# TSAL_Proto18_rev3_1.net
KiCad netlist of a schematic drawn in EAGLE
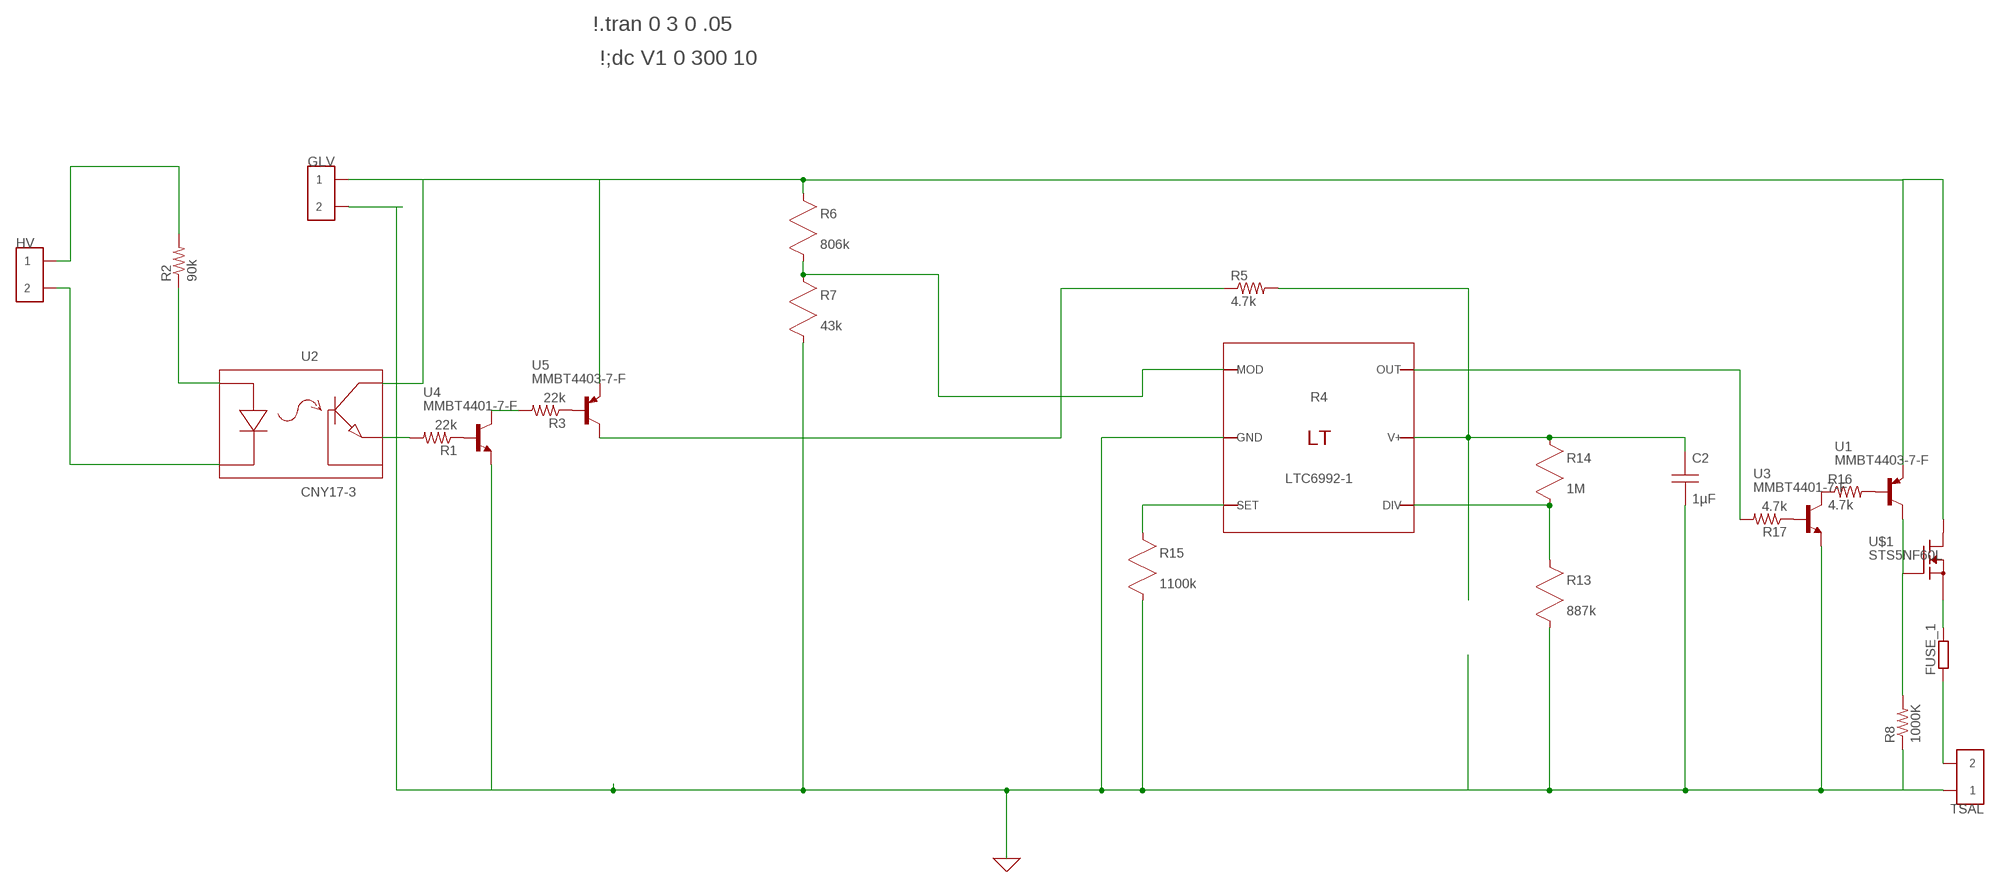
[diagram p0: schematic, sheet 1]

(export (version "E")
  (design (tool "Eeschema 10.0.6"))
  (components
    (comp (ref "C2")
      (value "1µF")
      (footprint "eagle-import:C0805")
      (libsource (lib "eagle-import") (part "CAP"))
    )
    (comp (ref "FUSE_1")
      (value "R-EU_R0402")
      (footprint "eagle-import:R0402")
      (libsource (lib "eagle-import") (part "R-EU_R0402"))
    )
    (comp (ref "GLV")
      (value "CONN_2")
      (footprint "eagle-import:CONNECTOR_2")
      (libsource (lib "eagle-import") (part "CONN_2"))
    )
    (comp (ref "HV")
      (value "CONN_2")
      (footprint "eagle-import:CONNECTOR_2")
      (libsource (lib "eagle-import") (part "CONN_2"))
    )
    (comp (ref "R1")
      (value "22k")
      (footprint "eagle-import:R0402")
      (libsource (lib "eagle-import") (part "R-US_R0402"))
    )
    (comp (ref "R2")
      (value "90k")
      (footprint "eagle-import:P0817_22")
      (libsource (lib "eagle-import") (part "R-US_0817/22"))
    )
    (comp (ref "R3")
      (value "22k")
      (footprint "eagle-import:R0402")
      (libsource (lib "eagle-import") (part "R-US_R0402"))
    )
    (comp (ref "R4")
      (value "LTC6992-1")
      (footprint "eagle-import:LTC6992-1")
      (libsource (lib "eagle-import") (part "LTC6992-1"))
    )
    (comp (ref "R5")
      (value "4.7k")
      (footprint "eagle-import:0805")
      (libsource (lib "eagle-import") (part "RESISTOR0805-RES"))
    )
    (comp (ref "R6")
      (value "806k")
      (footprint "eagle-import:R0805")
      (libsource (lib "eagle-import") (part "RES"))
    )
    (comp (ref "R7")
      (value "43k")
      (footprint "eagle-import:R0805")
      (libsource (lib "eagle-import") (part "RES"))
    )
    (comp (ref "R8")
      (value "1000K")
      (footprint "eagle-import:0805")
      (libsource (lib "eagle-import") (part "RESISTOR0805-RES"))
    )
    (comp (ref "R13")
      (value "887k")
      (footprint "eagle-import:R0805")
      (libsource (lib "eagle-import") (part "RES"))
    )
    (comp (ref "R14")
      (value "1M")
      (footprint "eagle-import:R0805")
      (libsource (lib "eagle-import") (part "RES"))
    )
    (comp (ref "R15")
      (value "1100k")
      (footprint "eagle-import:R0805")
      (libsource (lib "eagle-import") (part "RES"))
    )
    (comp (ref "R16")
      (value "4.7k")
      (footprint "eagle-import:R0402")
      (libsource (lib "eagle-import") (part "R-US_R0402"))
    )
    (comp (ref "R17")
      (value "4.7k")
      (footprint "eagle-import:R0402")
      (libsource (lib "eagle-import") (part "R-US_R0402"))
    )
    (comp (ref "TSAL")
      (value "CONN_2")
      (footprint "eagle-import:CONNECTOR_2")
      (libsource (lib "eagle-import") (part "CONN_2"))
    )
    (comp (ref "U$1")
      (value "STS5NF60L")
      (footprint "eagle-import:SO08")
      (libsource (lib "eagle-import") (part "STS5NF60L"))
    )
    (comp (ref "U1")
      (value "MMBT4403-7-F")
      (footprint "eagle-import:SOT-23-3")
      (libsource (lib "eagle-import") (part "MMBT4403-7-F"))
    )
    (comp (ref "U2")
      (value "CNY17-3")
      (footprint "eagle-import:CNY17-3")
      (libsource (lib "eagle-import") (part "CNY17-3"))
    )
    (comp (ref "U3")
      (value "MMBT4401-7-F")
      (footprint "eagle-import:SOT-23-3")
      (libsource (lib "eagle-import") (part "MMBT4401-7-F"))
    )
    (comp (ref "U4")
      (value "MMBT4401-7-F")
      (footprint "eagle-import:SOT-23-3")
      (libsource (lib "eagle-import") (part "MMBT4401-7-F"))
    )
    (comp (ref "U5")
      (value "MMBT4403-7-F")
      (footprint "eagle-import:SOT-23-3")
      (libsource (lib "eagle-import") (part "MMBT4403-7-F"))
    )
  )
  (nets
    (net (code "1") (name "0") (class "Default")
      (node (ref "C2") (pin "2") (pinfunction "B_2") (pintype "passive"))
      (node (ref "GLV") (pin "3") (pinfunction "2_3") (pintype "bidirectional"))
      (node (ref "GLV") (pin "4") (pinfunction "2_4") (pintype "bidirectional"))
      (node (ref "R13") (pin "2") (pinfunction "B_2") (pintype "passive"))
      (node (ref "R15") (pin "2") (pinfunction "B_2") (pintype "passive"))
      (node (ref "R4") (pin "P$2") (pinfunction "GND_P$2") (pintype "passive"))
      (node (ref "R7") (pin "2") (pinfunction "B_2") (pintype "passive"))
      (node (ref "R8") (pin "1") (pinfunction "1_1") (pintype "passive"))
      (node (ref "TSAL") (pin "1") (pinfunction "1_1") (pintype "bidirectional"))
      (node (ref "TSAL") (pin "2") (pinfunction "1_2") (pintype "bidirectional"))
      (node (ref "U3") (pin "P$3") (pinfunction "E_P$3") (pintype "passive"))
      (node (ref "U4") (pin "P$3") (pinfunction "E_P$3") (pintype "passive"))
    )
    (net (code "2") (name "Net-(C2-A)") (class "Default")
      (node (ref "C2") (pin "1") (pinfunction "A_1") (pintype "passive"))
      (node (ref "R14") (pin "1") (pinfunction "A_1") (pintype "passive"))
      (node (ref "R4") (pin "P$5") (pinfunction "V+_P$5") (pintype "passive"))
      (node (ref "R5") (pin "2") (pinfunction "2_2") (pintype "passive"))
    )
    (net (code "3") (name "Net-(FUSE_1-Pad1)") (class "Default")
      (node (ref "FUSE_1") (pin "1") (pinfunction "1_1") (pintype "passive"))
      (node (ref "TSAL") (pin "3") (pinfunction "2_3") (pintype "bidirectional"))
      (node (ref "TSAL") (pin "4") (pinfunction "2_4") (pintype "bidirectional"))
    )
    (net (code "4") (name "Net-(FUSE_1-Pad2)") (class "Default")
      (node (ref "FUSE_1") (pin "2") (pinfunction "2_2") (pintype "passive"))
      (node (ref "U$1") (pin "1") (pinfunction "S_1") (pintype "passive"))
      (node (ref "U$1") (pin "2") (pinfunction "S_2") (pintype "passive"))
      (node (ref "U$1") (pin "3") (pinfunction "S_3") (pintype "passive"))
    )
    (net (code "5") (name "Net-(HV-1-Pad2)") (class "Default")
      (node (ref "HV") (pin "1") (pinfunction "1_1") (pintype "bidirectional"))
      (node (ref "HV") (pin "2") (pinfunction "1_2") (pintype "bidirectional"))
      (node (ref "R2") (pin "2") (pinfunction "2_2") (pintype "passive"))
    )
    (net (code "6") (name "Net-(R4-MOD)") (class "Default")
      (node (ref "R4") (pin "P$1") (pinfunction "MOD_P$1") (pintype "passive"))
      (node (ref "R6") (pin "2") (pinfunction "B_2") (pintype "passive"))
      (node (ref "R7") (pin "1") (pinfunction "A_1") (pintype "passive"))
    )
    (net (code "7") (name "Net-(R4-OUT)") (class "Default")
      (node (ref "R17") (pin "2") (pinfunction "2_2") (pintype "passive"))
      (node (ref "R4") (pin "P$6") (pinfunction "OUT_P$6") (pintype "passive"))
    )
    (net (code "8") (name "Net-(R6-A)") (class "Default")
      (node (ref "GLV") (pin "1") (pinfunction "1_1") (pintype "bidirectional"))
      (node (ref "GLV") (pin "2") (pinfunction "1_2") (pintype "bidirectional"))
      (node (ref "R6") (pin "1") (pinfunction "A_1") (pintype "passive"))
      (node (ref "U$1") (pin "5") (pinfunction "D_5") (pintype "passive"))
      (node (ref "U$1") (pin "6") (pinfunction "D_6") (pintype "passive"))
      (node (ref "U$1") (pin "7") (pinfunction "D_7") (pintype "passive"))
      (node (ref "U$1") (pin "8") (pinfunction "D_8") (pintype "passive"))
      (node (ref "U1") (pin "P$3") (pinfunction "E_P$3") (pintype "passive"))
      (node (ref "U2") (pin "P$5") (pinfunction "C_P$5") (pintype "passive"))
      (node (ref "U5") (pin "P$3") (pinfunction "E_P$3") (pintype "passive"))
    )
    (net (code "9") (name "Net-(R13-A)") (class "Default")
      (node (ref "R13") (pin "1") (pinfunction "A_1") (pintype "passive"))
      (node (ref "R14") (pin "2") (pinfunction "B_2") (pintype "passive"))
      (node (ref "R4") (pin "P$4") (pinfunction "DIV_P$4") (pintype "passive"))
    )
    (net (code "10") (name "Net-(R15-A)") (class "Default")
      (node (ref "R15") (pin "1") (pinfunction "A_1") (pintype "passive"))
      (node (ref "R4") (pin "P$3") (pinfunction "SET_P$3") (pintype "passive"))
    )
    (net (code "11") (name "Net-(U$1-G)") (class "Default")
      (node (ref "R8") (pin "2") (pinfunction "2_2") (pintype "passive"))
      (node (ref "U$1") (pin "4") (pinfunction "G_4") (pintype "passive"))
      (node (ref "U1") (pin "P$1") (pinfunction "C_P$1") (pintype "passive"))
    )
    (net (code "12") (name "Net-(U1-B)") (class "Default")
      (node (ref "R16") (pin "2") (pinfunction "2_2") (pintype "passive"))
      (node (ref "U1") (pin "P$2") (pinfunction "B_P$2") (pintype "passive"))
    )
    (net (code "13") (name "Net-(U2-A)") (class "Default")
      (node (ref "R2") (pin "1") (pinfunction "1_1") (pintype "passive"))
      (node (ref "U2") (pin "P$1") (pinfunction "A_P$1") (pintype "passive"))
    )
    (net (code "14") (name "Net-(U2-E)") (class "Default")
      (node (ref "R1") (pin "2") (pinfunction "2_2") (pintype "passive"))
      (node (ref "U2") (pin "P$4") (pinfunction "E_P$4") (pintype "passive"))
    )
    (net (code "15") (name "Net-(U2-K)") (class "Default")
      (node (ref "HV") (pin "3") (pinfunction "2_3") (pintype "bidirectional"))
      (node (ref "HV") (pin "4") (pinfunction "2_4") (pintype "bidirectional"))
      (node (ref "U2") (pin "P$2") (pinfunction "K_P$2") (pintype "passive"))
    )
    (net (code "16") (name "Net-(U3-B)") (class "Default")
      (node (ref "R17") (pin "1") (pinfunction "1_1") (pintype "passive"))
      (node (ref "U3") (pin "P$2") (pinfunction "B_P$2") (pintype "passive"))
    )
    (net (code "17") (name "Net-(U3-C)") (class "Default")
      (node (ref "R16") (pin "1") (pinfunction "1_1") (pintype "passive"))
      (node (ref "U3") (pin "P$1") (pinfunction "C_P$1") (pintype "passive"))
    )
    (net (code "18") (name "Net-(U4-B)") (class "Default")
      (node (ref "R1") (pin "1") (pinfunction "1_1") (pintype "passive"))
      (node (ref "U4") (pin "P$2") (pinfunction "B_P$2") (pintype "passive"))
    )
    (net (code "19") (name "Net-(U4-C)") (class "Default")
      (node (ref "R3") (pin "2") (pinfunction "2_2") (pintype "passive"))
      (node (ref "U4") (pin "P$1") (pinfunction "C_P$1") (pintype "passive"))
    )
    (net (code "20") (name "Net-(U5-B)") (class "Default")
      (node (ref "R3") (pin "1") (pinfunction "1_1") (pintype "passive"))
      (node (ref "U5") (pin "P$2") (pinfunction "B_P$2") (pintype "passive"))
    )
    (net (code "21") (name "Net-(U5-C)") (class "Default")
      (node (ref "R5") (pin "1") (pinfunction "1_1") (pintype "passive"))
      (node (ref "U5") (pin "P$1") (pinfunction "C_P$1") (pintype "passive"))
    )
    (net (code "22") (name "unconnected-(U2-B-PadP$6)") (class "Default")
      (node (ref "U2") (pin "P$6") (pinfunction "B_P$6") (pintype "passive"))
    )
  )
)
